# Barrier_control.net
KiCad netlist of a schematic drawn in Altium Designer
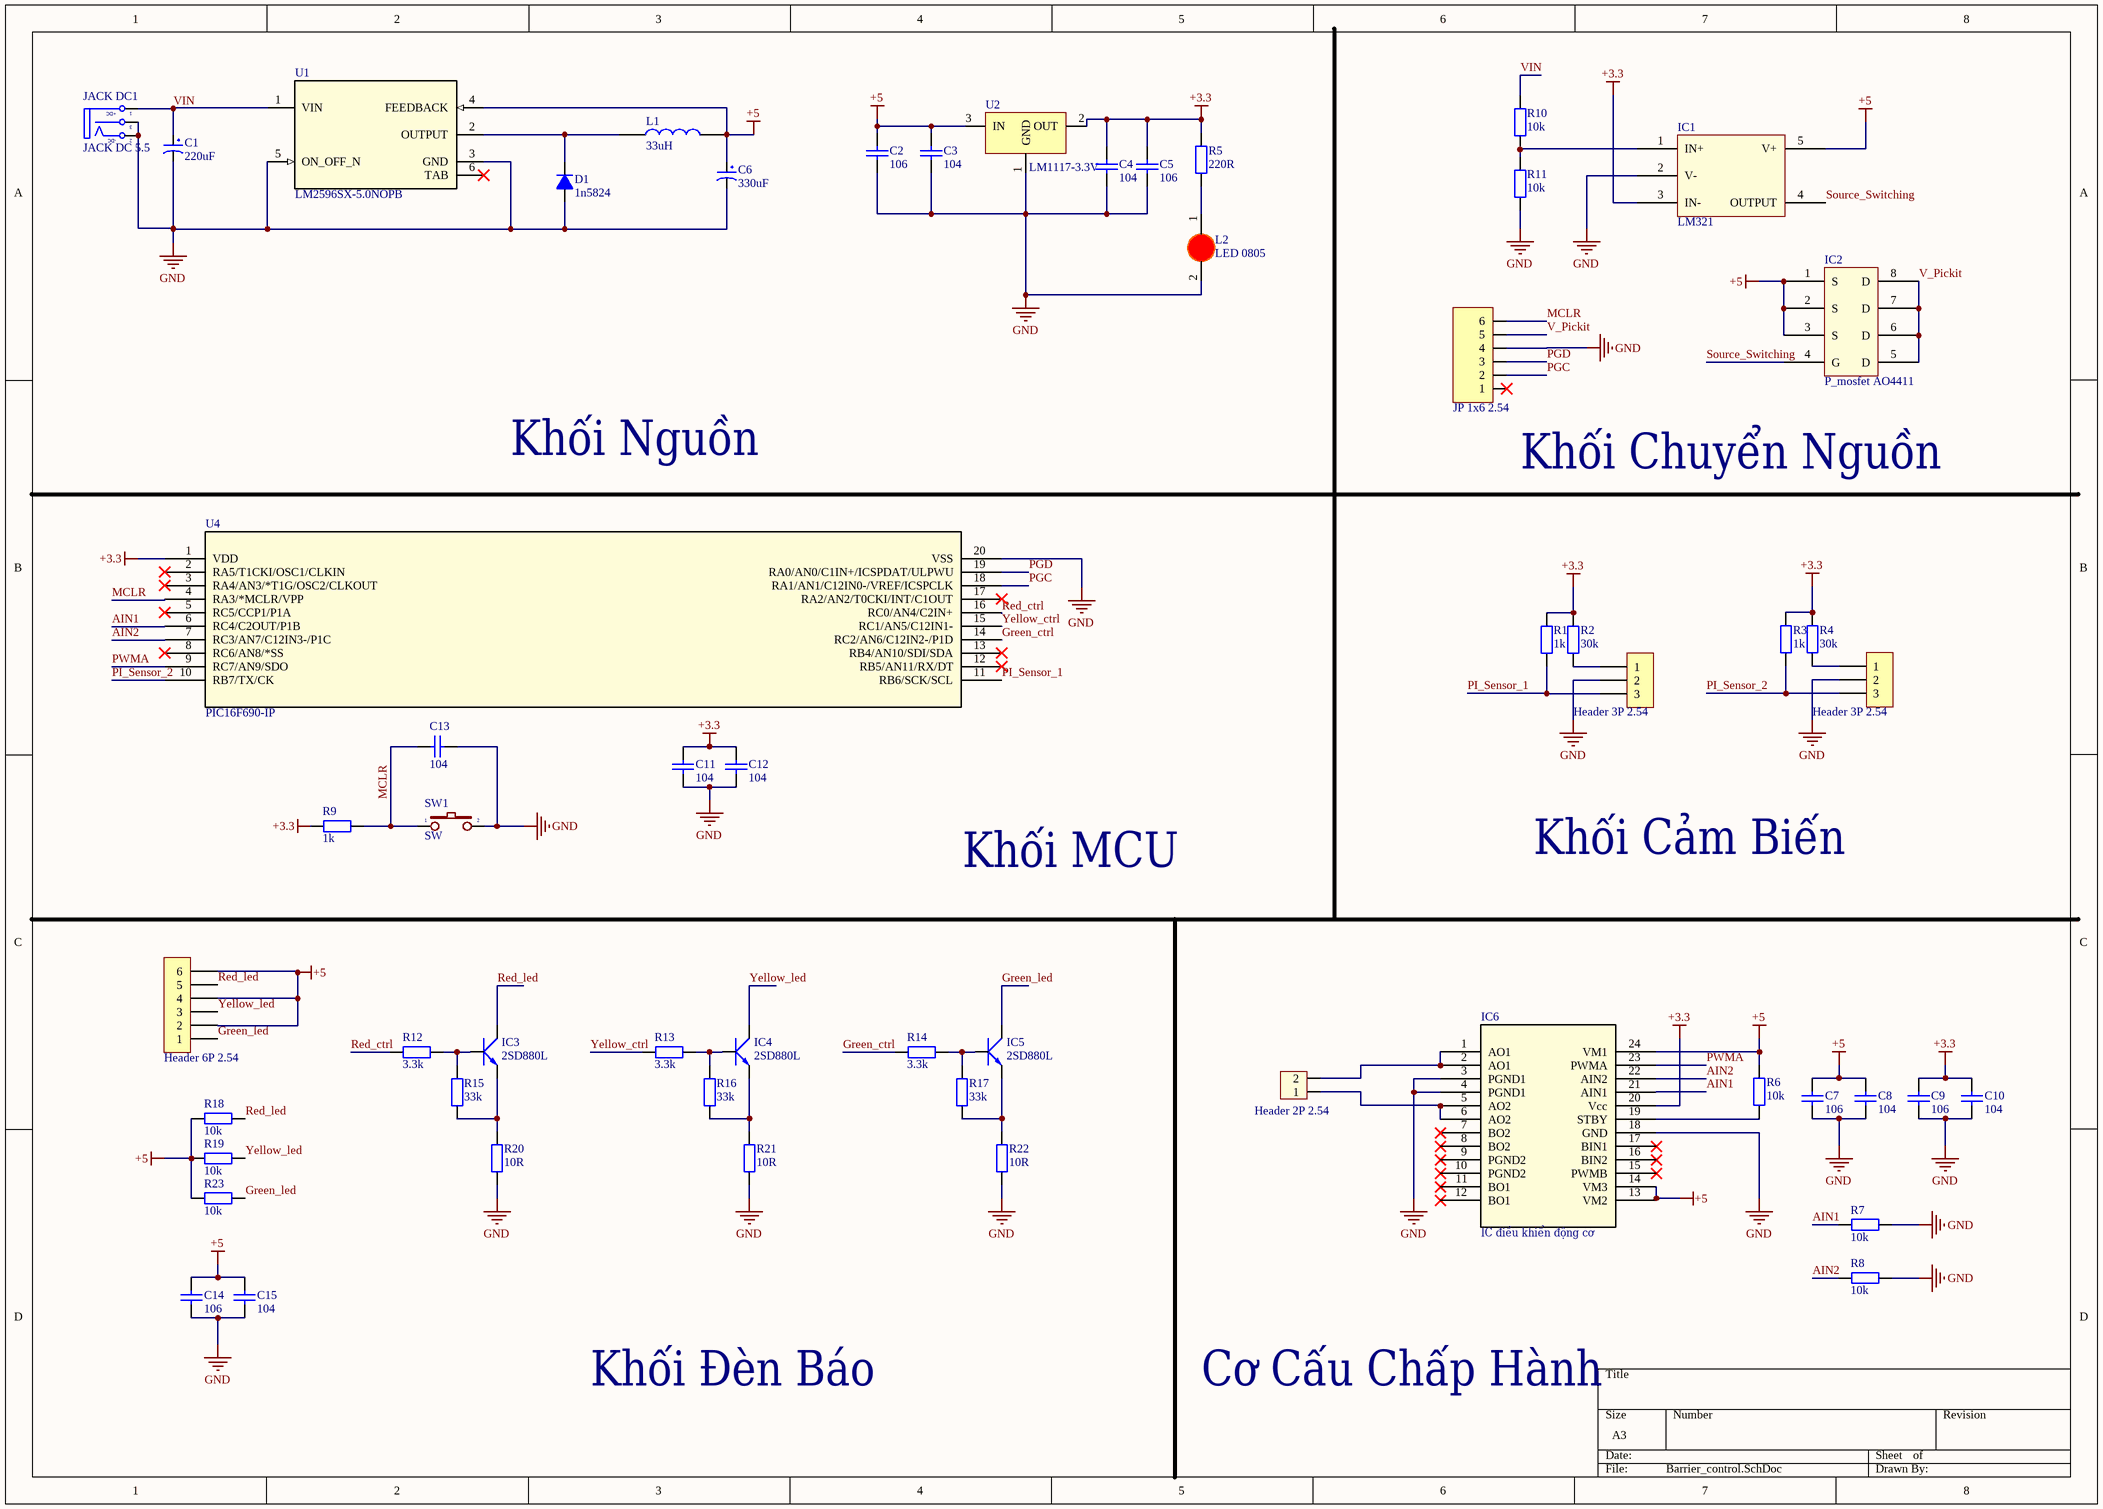
[diagram p0: Barrier_control.SchDoc]

(export (version "E")
  (design (tool "Eeschema 10.0.6"))
  (components
    (comp (ref "C1")
      (value "220uF")
      (footprint "tu hoa 6.5mm")
      (description "Cắm")
      (libsource (lib "Altium_Lib_by_KhueNguyenCreator") (part "Tu Hoa 220uF 16V 7x11"))
    )
    (comp (ref "C2")
      (value "106")
      (footprint "tu 1206")
      (description "Dán")
      (libsource (lib "Altium_Lib_by_KhueNguyenCreator") (part "Tu 1206 106 16V 20%"))
    )
    (comp (ref "C3")
      (value "104")
      (footprint "tu 1206")
      (description "Dán")
      (libsource (lib "Altium_Lib_by_KhueNguyenCreator") (part "Tu 1206 104 50V 20%"))
    )
    (comp (ref "C4")
      (value "104")
      (footprint "tu 1206")
      (description "Dán")
      (libsource (lib "Altium_Lib_by_KhueNguyenCreator") (part "Tu 1206 104 50V 20%"))
    )
    (comp (ref "C5")
      (value "106")
      (footprint "tu 1206")
      (description "Dán")
      (libsource (lib "Altium_Lib_by_KhueNguyenCreator") (part "Tu 1206 106 16V 20%"))
    )
    (comp (ref "C6")
      (value "330uF")
      (footprint "tu hoa 10mm")
      (description "Cắm")
      (libsource (lib "Altium_Lib_by_KhueNguyenCreator") (part "Tu Hoa 330uF 35V 10x12"))
    )
    (comp (ref "C7")
      (value "106")
      (footprint "tu 1206")
      (description "Dán")
      (libsource (lib "Altium_Lib_by_KhueNguyenCreator") (part "Tu 1206 106 16V 20%"))
    )
    (comp (ref "C8")
      (value "104")
      (footprint "tu 1206")
      (description "Dán")
      (libsource (lib "Altium_Lib_by_KhueNguyenCreator") (part "Tu 1206 104 50V 20%"))
    )
    (comp (ref "C9")
      (value "106")
      (footprint "tu 1206")
      (description "Dán")
      (libsource (lib "Altium_Lib_by_KhueNguyenCreator") (part "Tu 1206 106 16V 20%"))
    )
    (comp (ref "C10")
      (value "104")
      (footprint "tu 1206")
      (description "Dán")
      (libsource (lib "Altium_Lib_by_KhueNguyenCreator") (part "Tu 1206 104 50V 20%"))
    )
    (comp (ref "C11")
      (value "104")
      (footprint "tu 0805")
      (description "Dán")
      (libsource (lib "Altium_Lib_by_KhueNguyenCreator") (part "Tu 0805 104 50V 10%"))
    )
    (comp (ref "C12")
      (value "104")
      (footprint "tu 0805")
      (description "Dán")
      (libsource (lib "Altium_Lib_by_KhueNguyenCreator") (part "Tu 0805 104 50V 10%"))
    )
    (comp (ref "C13")
      (value "104")
      (footprint "tu gom")
      (description "Cắm")
      (libsource (lib "Altium_Lib_by_KhueNguyenCreator") (part "Tu gom 104 50V"))
    )
    (comp (ref "C14")
      (value "106")
      (footprint "tu 1206")
      (description "Dán")
      (libsource (lib "Altium_Lib_by_KhueNguyenCreator") (part "Tu 1206 106 16V 20%"))
    )
    (comp (ref "C15")
      (value "104")
      (footprint "tu 1206")
      (description "Dán")
      (libsource (lib "Altium_Lib_by_KhueNguyenCreator") (part "Tu 1206 104 50V 20%"))
    )
    (comp (ref "D1")
      (value "1n5824")
      (footprint "DIODE 1A")
      (description "Cắm")
      (libsource (lib "Altium_Lib_by_KhueNguyenCreator") (part "Diode 1N4007"))
    )
    (comp (ref "H1")
      (value "Header 3P 2.54")
      (footprint "XH2.54M-3")
      (description "Cắm")
      (libsource (lib "Altium_Lib_by_KhueNguyenCreator") (part "Header 3P 2.54 Duc Thang"))
    )
    (comp (ref "H2")
      (value "Header 3P 2.54")
      (footprint "XH2.54M-3")
      (description "Cắm")
      (libsource (lib "Altium_Lib_by_KhueNguyenCreator") (part "Header 3P 2.54 Duc Thang"))
    )
    (comp (ref "H3")
      (value "Header 2P 2.54")
      (footprint "XH2.54M-2")
      (description "Cắm")
      (libsource (lib "Altium_Lib_by_KhueNguyenCreator") (part "Header 2P 2.54 Duc Thang"))
    )
    (comp (ref "H4")
      (value "Header 6P 2.54")
      (footprint "XH2.54M-6")
      (description "Cắm")
      (libsource (lib "Altium_Lib_by_KhueNguyenCreator") (part "Header 6P 2.54 Duc Thang"))
    )
    (comp (ref "IC1") (value "LM321") (footprint "SOT23_LM321") (libsource (lib "Schlib2") (part "LM321")))
    (comp (ref "IC2")
      (value "P_mosfet AO4411")
      (footprint "SOIC8_AO4411")
      (libsource (lib "AO4411") (part "P_mosfet AO4411"))
    )
    (comp (ref "IC3")
      (value "2SD880L")
      (footprint "TO220")
      (libsource (lib "tran_npn_2SD880L") (part "transistor NPN"))
    )
    (comp (ref "IC4")
      (value "2SD880L")
      (footprint "TO220")
      (libsource (lib "tran_npn_2SD880L") (part "transistor NPN"))
    )
    (comp (ref "IC5")
      (value "2SD880L")
      (footprint "TO220")
      (libsource (lib "tran_npn_2SD880L") (part "transistor NPN"))
    )
    (comp (ref "IC6")
      (value "IC điều khiển động cơ")
      (footprint "SSOP24-P-300-0p65A_TOS")
      (libsource (lib "TB6612") (part "TB6612FNG"))
    )
    (comp (ref "JACK DC1")
      (value "JACK DC 5.5")
      (footprint "JACK DC 5.5")
      (libsource (lib "Altium_Lib_by_KhueNguyenCreator") (part "JACK DC 5.5"))
    )
    (comp (ref "JP1")
      (value "JP 1x6 2.54")
      (footprint "JP 1x6 DC")
      (description "Cắm")
      (libsource (lib "Altium_Lib_by_KhueNguyenCreator") (part "JP 1x6 2.54 Duc Cong"))
    )
    (comp (ref "L1")
      (value "33uH")
      (footprint "Cuon Cam 12x12x10")
      (description "Dán")
      (libsource (lib "Altium_Lib_by_KhueNguyenCreator") (part "CUON CAM 100uH SMD"))
    )
    (comp (ref "L2")
      (value "LED 0805")
      (footprint "LED-0805-Red")
      (description "Dán")
      (libsource (lib "Altium_Lib_by_KhueNguyenCreator") (part "LED 0805 Do"))
    )
    (comp (ref "R1")
      (value "1k")
      (footprint "tro smd 0805")
      (description "Dán")
      (libsource (lib "Altium_Lib_by_KhueNguyenCreator") (part "Tro 0805 1% 1k"))
    )
    (comp (ref "R2")
      (value "30k")
      (footprint "tro smd 0805")
      (description "Dán")
      (libsource (lib "Altium_Lib_by_KhueNguyenCreator") (part "Tro 0805 1% 33k"))
    )
    (comp (ref "R3")
      (value "1k")
      (footprint "tro smd 0805")
      (description "Dán")
      (libsource (lib "Altium_Lib_by_KhueNguyenCreator") (part "Tro 0805 1% 1k"))
    )
    (comp (ref "R4")
      (value "30k")
      (footprint "tro smd 0805")
      (description "Dán")
      (libsource (lib "Altium_Lib_by_KhueNguyenCreator") (part "Tro 0805 1% 33k"))
    )
    (comp (ref "R5")
      (value "220R")
      (footprint "tro smd 0805")
      (description "Dán")
      (libsource (lib "Altium_Lib_by_KhueNguyenCreator") (part "Tro 0805 1% 0.5R"))
    )
    (comp (ref "R6")
      (value "10k")
      (footprint "tro smd 0805")
      (description "Dán")
      (libsource (lib "Altium_Lib_by_KhueNguyenCreator") (part "Tro 0805 1% 10k"))
    )
    (comp (ref "R7")
      (value "10k")
      (footprint "tro smd 0805")
      (description "Dán")
      (libsource (lib "Altium_Lib_by_KhueNguyenCreator") (part "Tro 0805 1% 10k"))
    )
    (comp (ref "R8")
      (value "10k")
      (footprint "tro smd 0805")
      (description "Dán")
      (libsource (lib "Altium_Lib_by_KhueNguyenCreator") (part "Tro 0805 1% 10k"))
    )
    (comp (ref "R9")
      (value "1k")
      (footprint "tro smd 0805")
      (description "Dán")
      (libsource (lib "Altium_Lib_by_KhueNguyenCreator") (part "Tro 0805 1% 1k"))
    )
    (comp (ref "R10")
      (value "10k")
      (footprint "tro smd 0805")
      (description "Dán")
      (libsource (lib "Altium_Lib_by_KhueNguyenCreator") (part "Tro 0805 1% 10k"))
    )
    (comp (ref "R11")
      (value "10k")
      (footprint "tro smd 0805")
      (description "Dán")
      (libsource (lib "Altium_Lib_by_KhueNguyenCreator") (part "Tro 0805 1% 10k"))
    )
    (comp (ref "R12")
      (value "3.3k")
      (footprint "tro smd 0805")
      (description "Dán")
      (libsource (lib "Altium_Lib_by_KhueNguyenCreator") (part "Tro 0805 1% 3.3k"))
    )
    (comp (ref "R13")
      (value "3.3k")
      (footprint "tro smd 0805")
      (description "Dán")
      (libsource (lib "Altium_Lib_by_KhueNguyenCreator") (part "Tro 0805 1% 3.3k"))
    )
    (comp (ref "R14")
      (value "3.3k")
      (footprint "tro smd 0805")
      (description "Dán")
      (libsource (lib "Altium_Lib_by_KhueNguyenCreator") (part "Tro 0805 1% 3.3k"))
    )
    (comp (ref "R15")
      (value "33k")
      (footprint "tro smd 0805")
      (description "Dán")
      (libsource (lib "Altium_Lib_by_KhueNguyenCreator") (part "Tro 0805 1% 33k"))
    )
    (comp (ref "R16")
      (value "33k")
      (footprint "tro smd 0805")
      (description "Dán")
      (libsource (lib "Altium_Lib_by_KhueNguyenCreator") (part "Tro 0805 1% 33k"))
    )
    (comp (ref "R17")
      (value "33k")
      (footprint "tro smd 0805")
      (description "Dán")
      (libsource (lib "Altium_Lib_by_KhueNguyenCreator") (part "Tro 0805 1% 33k"))
    )
    (comp (ref "R18")
      (value "10k")
      (footprint "tro smd 0805")
      (description "Dán")
      (libsource (lib "Altium_Lib_by_KhueNguyenCreator") (part "Tro 0805 1% 10k"))
    )
    (comp (ref "R19")
      (value "10k")
      (footprint "tro smd 0805")
      (description "Dán")
      (libsource (lib "Altium_Lib_by_KhueNguyenCreator") (part "Tro 0805 1% 10k"))
    )
    (comp (ref "R20")
      (value "10R")
      (footprint "tro smd 0805")
      (description "Dán")
      (libsource (lib "Altium_Lib_by_KhueNguyenCreator") (part "Tro 0805 1% 10R"))
    )
    (comp (ref "R21")
      (value "10R")
      (footprint "tro smd 0805")
      (description "Dán")
      (libsource (lib "Altium_Lib_by_KhueNguyenCreator") (part "Tro 0805 1% 10R"))
    )
    (comp (ref "R22")
      (value "10R")
      (footprint "tro smd 0805")
      (description "Dán")
      (libsource (lib "Altium_Lib_by_KhueNguyenCreator") (part "Tro 0805 1% 10R"))
    )
    (comp (ref "R23")
      (value "10k")
      (footprint "tro smd 0805")
      (description "Dán")
      (libsource (lib "Altium_Lib_by_KhueNguyenCreator") (part "Tro 0805 1% 10k"))
    )
    (comp (ref "SW1")
      (value "SW")
      (footprint "SW2")
      (description "Switch button 2 pin")
      (libsource (lib "syhaunguyen") (part "SW2"))
    )
    (comp (ref "U1")
      (value "LM2596SX-5.0NOPB")
      (footprint "KTT0005B")
      (description "No Description Available")
      (fields
        (field (name "PARTNUMBER") "LM2596SX-ADJ/NOPB")
        (field (name "ALTERNATE_PARTNUMBER") "LM2596S-ADJ/NOPB")
      )
      (libsource (lib "LM2596SX-5P0NOPB") (part "LM2596SX-5.0NOPB"))
    )
    (comp (ref "U2")
      (value "LM1117-3.3V")
      (footprint "LM1117-SOP")
      (description "800mA Low-Dropout Linear Regulator")
      (fields (field (name "CREATOR") "Nguyen Ba Bien"))
      (libsource (lib "My library altium") (part "LM1117"))
    )
    (comp (ref "U4")
      (value "PIC16F690-IP")
      (footprint "PDIP20_300MC_MCH")
      (description "No Description Available")
      (libsource (lib "PIC16F690-IP") (part "PIC16F690-IP"))
    )
  )
  (nets
    (net (code "1") (name "+3.3") (class "Default")
      (node (ref "C10") (pin "1") (pinfunction "1_1") (pintype "passive"))
      (node (ref "C11") (pin "1") (pinfunction "1_1") (pintype "passive"))
      (node (ref "C12") (pin "1") (pinfunction "1_1") (pintype "passive"))
      (node (ref "C4") (pin "1") (pinfunction "1_1") (pintype "passive"))
      (node (ref "C5") (pin "2") (pinfunction "2_2") (pintype "passive"))
      (node (ref "C9") (pin "2") (pinfunction "2_2") (pintype "passive"))
      (node (ref "IC1") (pin "3") (pinfunction "IN-_3") (pintype "passive"))
      (node (ref "IC6") (pin "20") (pinfunction "Vcc_20") (pintype "passive"))
      (node (ref "R1") (pin "2") (pinfunction "2_2") (pintype "passive"))
      (node (ref "R2") (pin "2") (pinfunction "2_2") (pintype "passive"))
      (node (ref "R3") (pin "2") (pinfunction "2_2") (pintype "passive"))
      (node (ref "R4") (pin "2") (pinfunction "2_2") (pintype "passive"))
      (node (ref "R5") (pin "1") (pinfunction "1_1") (pintype "passive"))
      (node (ref "R9") (pin "2") (pinfunction "2_2") (pintype "passive"))
      (node (ref "U2") (pin "2") (pinfunction "OUT_2") (pintype "passive"))
      (node (ref "U4") (pin "1") (pinfunction "VDD_1") (pintype "passive"))
    )
    (net (code "2") (name "+5") (class "Default")
      (node (ref "C14") (pin "2") (pinfunction "2_2") (pintype "passive"))
      (node (ref "C15") (pin "1") (pinfunction "1_1") (pintype "passive"))
      (node (ref "C2") (pin "2") (pinfunction "2_2") (pintype "passive"))
      (node (ref "C3") (pin "1") (pinfunction "1_1") (pintype "passive"))
      (node (ref "C6") (pin "1") (pinfunction "1_1") (pintype "passive"))
      (node (ref "C7") (pin "2") (pinfunction "2_2") (pintype "passive"))
      (node (ref "C8") (pin "1") (pinfunction "1_1") (pintype "passive"))
      (node (ref "H4") (pin "2") (pinfunction "2_2") (pintype "passive"))
      (node (ref "H4") (pin "4") (pinfunction "4_4") (pintype "passive"))
      (node (ref "H4") (pin "6") (pinfunction "6_6") (pintype "passive"))
      (node (ref "IC1") (pin "5") (pinfunction "V+_5") (pintype "passive"))
      (node (ref "IC2") (pin "1") (pinfunction "S_1") (pintype "passive"))
      (node (ref "IC2") (pin "2") (pinfunction "S_2") (pintype "passive"))
      (node (ref "IC2") (pin "3") (pinfunction "S_3") (pintype "passive"))
      (node (ref "IC6") (pin "13") (pinfunction "VM2_13") (pintype "passive"))
      (node (ref "IC6") (pin "14") (pinfunction "VM3_14") (pintype "passive"))
      (node (ref "IC6") (pin "24") (pinfunction "VM1_24") (pintype "passive"))
      (node (ref "L1") (pin "2") (pinfunction "2_2") (pintype "passive"))
      (node (ref "R18") (pin "2") (pinfunction "2_2") (pintype "passive"))
      (node (ref "R19") (pin "2") (pinfunction "2_2") (pintype "passive"))
      (node (ref "R23") (pin "2") (pinfunction "2_2") (pintype "passive"))
      (node (ref "R6") (pin "2") (pinfunction "2_2") (pintype "passive"))
      (node (ref "U1") (pin "4") (pinfunction "FEEDBACK_4") (pintype "input"))
      (node (ref "U2") (pin "3") (pinfunction "IN_3") (pintype "passive"))
    )
    (net (code "3") (name "/AIN1") (class "Default")
      (node (ref "IC6") (pin "21") (pinfunction "AIN1_21") (pintype "passive"))
      (node (ref "R7") (pin "2") (pinfunction "2_2") (pintype "passive"))
      (node (ref "U4") (pin "6") (pinfunction "RC4/C2OUT/P1B_6") (pintype "passive"))
    )
    (net (code "4") (name "/AIN2") (class "Default")
      (node (ref "IC6") (pin "22") (pinfunction "AIN2_22") (pintype "passive"))
      (node (ref "R8") (pin "2") (pinfunction "2_2") (pintype "passive"))
      (node (ref "U4") (pin "7") (pinfunction "RC3/AN7/C12IN3-/P1C_7") (pintype "passive"))
    )
    (net (code "5") (name "/Green_ctrl") (class "Default")
      (node (ref "R14") (pin "1") (pinfunction "1_1") (pintype "passive"))
      (node (ref "U4") (pin "14") (pinfunction "RC2/AN6/C12IN2-/P1D_14") (pintype "passive"))
    )
    (net (code "6") (name "/Green_led") (class "Default")
      (node (ref "H4") (pin "1") (pinfunction "1_1") (pintype "passive"))
      (node (ref "IC5") (pin "3") (pinfunction "C_3") (pintype "passive"))
      (node (ref "R23") (pin "1") (pinfunction "1_1") (pintype "passive"))
    )
    (net (code "7") (name "/MCLR") (class "Default")
      (node (ref "C13") (pin "1") (pinfunction "1_1") (pintype "passive"))
      (node (ref "JP1") (pin "6") (pinfunction "6_6") (pintype "passive"))
      (node (ref "R9") (pin "1") (pinfunction "1_1") (pintype "passive"))
      (node (ref "SW1") (pin "1") (pinfunction "1_1") (pintype "passive"))
      (node (ref "U4") (pin "4") (pinfunction "RA3/*MCLR/VPP_4") (pintype "passive"))
    )
    (net (code "8") (name "/PGC") (class "Default")
      (node (ref "JP1") (pin "2") (pinfunction "2_2") (pintype "passive"))
      (node (ref "U4") (pin "18") (pinfunction "RA1/AN1/C12IN0-/VREF/ICSPCLK_18") (pintype "passive"))
    )
    (net (code "9") (name "/PGD") (class "Default")
      (node (ref "JP1") (pin "3") (pinfunction "3_3") (pintype "passive"))
      (node (ref "U4") (pin "19") (pinfunction "RA0/AN0/C1IN+/ICSPDAT/ULPWU_19") (pintype "passive"))
    )
    (net (code "10") (name "/PI_Sensor_1") (class "Default")
      (node (ref "H1") (pin "3") (pinfunction "3_3") (pintype "passive"))
      (node (ref "R1") (pin "1") (pinfunction "1_1") (pintype "passive"))
      (node (ref "U4") (pin "11") (pinfunction "RB6/SCK/SCL_11") (pintype "passive"))
    )
    (net (code "11") (name "/PI_Sensor_2") (class "Default")
      (node (ref "H2") (pin "3") (pinfunction "3_3") (pintype "passive"))
      (node (ref "R3") (pin "1") (pinfunction "1_1") (pintype "passive"))
      (node (ref "U4") (pin "10") (pinfunction "RB7/TX/CK_10") (pintype "passive"))
    )
    (net (code "12") (name "/PWMA") (class "Default")
      (node (ref "IC6") (pin "23") (pinfunction "PWMA_23") (pintype "passive"))
      (node (ref "U4") (pin "9") (pinfunction "RC7/AN9/SDO_9") (pintype "passive"))
    )
    (net (code "13") (name "/Red_ctrl") (class "Default")
      (node (ref "R12") (pin "1") (pinfunction "1_1") (pintype "passive"))
      (node (ref "U4") (pin "16") (pinfunction "RC0/AN4/C2IN+_16") (pintype "passive"))
    )
    (net (code "14") (name "/Red_led") (class "Default")
      (node (ref "H4") (pin "5") (pinfunction "5_5") (pintype "passive"))
      (node (ref "IC3") (pin "3") (pinfunction "C_3") (pintype "passive"))
      (node (ref "R18") (pin "1") (pinfunction "1_1") (pintype "passive"))
    )
    (net (code "15") (name "/Source_Switching") (class "Default")
      (node (ref "IC1") (pin "4") (pinfunction "OUTPUT_4") (pintype "passive"))
      (node (ref "IC2") (pin "4") (pinfunction "G_4") (pintype "passive"))
    )
    (net (code "16") (name "/VIN") (class "Default")
      (node (ref "C1") (pin "1") (pinfunction "1_1") (pintype "passive"))
      (node (ref "JACK DC1") (pin "1") (pinfunction "T_1") (pintype "passive"))
      (node (ref "R10") (pin "2") (pinfunction "2_2") (pintype "passive"))
      (node (ref "U1") (pin "1") (pinfunction "VIN_1") (pintype "power_in"))
    )
    (net (code "17") (name "/V_Pickit") (class "Default")
      (node (ref "IC2") (pin "5") (pinfunction "D_5") (pintype "passive"))
      (node (ref "IC2") (pin "6") (pinfunction "D_6") (pintype "passive"))
      (node (ref "IC2") (pin "7") (pinfunction "D_7") (pintype "passive"))
      (node (ref "IC2") (pin "8") (pinfunction "D_8") (pintype "passive"))
      (node (ref "JP1") (pin "5") (pinfunction "5_5") (pintype "passive"))
    )
    (net (code "18") (name "/Yellow_ctrl") (class "Default")
      (node (ref "R13") (pin "1") (pinfunction "1_1") (pintype "passive"))
      (node (ref "U4") (pin "15") (pinfunction "RC1/AN5/C12IN1-_15") (pintype "passive"))
    )
    (net (code "19") (name "/Yellow_led") (class "Default")
      (node (ref "H4") (pin "3") (pinfunction "3_3") (pintype "passive"))
      (node (ref "IC4") (pin "3") (pinfunction "C_3") (pintype "passive"))
      (node (ref "R19") (pin "1") (pinfunction "1_1") (pintype "passive"))
    )
    (net (code "20") (name "GND") (class "Default")
      (node (ref "C1") (pin "2") (pinfunction "2_2") (pintype "passive"))
      (node (ref "C10") (pin "2") (pinfunction "2_2") (pintype "passive"))
      (node (ref "C11") (pin "2") (pinfunction "2_2") (pintype "passive"))
      (node (ref "C12") (pin "2") (pinfunction "2_2") (pintype "passive"))
      (node (ref "C13") (pin "2") (pinfunction "2_2") (pintype "passive"))
      (node (ref "C14") (pin "1") (pinfunction "1_1") (pintype "passive"))
      (node (ref "C15") (pin "2") (pinfunction "2_2") (pintype "passive"))
      (node (ref "C2") (pin "1") (pinfunction "1_1") (pintype "passive"))
      (node (ref "C3") (pin "2") (pinfunction "2_2") (pintype "passive"))
      (node (ref "C4") (pin "2") (pinfunction "2_2") (pintype "passive"))
      (node (ref "C5") (pin "1") (pinfunction "1_1") (pintype "passive"))
      (node (ref "C6") (pin "2") (pinfunction "2_2") (pintype "passive"))
      (node (ref "C7") (pin "1") (pinfunction "1_1") (pintype "passive"))
      (node (ref "C8") (pin "2") (pinfunction "2_2") (pintype "passive"))
      (node (ref "C9") (pin "1") (pinfunction "1_1") (pintype "passive"))
      (node (ref "D1") (pin "1") (pinfunction "A_1") (pintype "passive"))
      (node (ref "H1") (pin "2") (pinfunction "2_2") (pintype "passive"))
      (node (ref "H2") (pin "2") (pinfunction "2_2") (pintype "passive"))
      (node (ref "IC1") (pin "2") (pinfunction "V-_2") (pintype "passive"))
      (node (ref "IC6") (pin "18") (pinfunction "GND_18") (pintype "passive"))
      (node (ref "IC6") (pin "3") (pinfunction "PGND1_3") (pintype "passive"))
      (node (ref "IC6") (pin "4") (pinfunction "PGND1_4") (pintype "passive"))
      (node (ref "JACK DC1") (pin "2") (pinfunction "TN_2") (pintype "passive"))
      (node (ref "JACK DC1") (pin "3") (pinfunction "S_3") (pintype "power_in"))
      (node (ref "JP1") (pin "4") (pinfunction "4_4") (pintype "passive"))
      (node (ref "L2") (pin "2") (pinfunction "K_2") (pintype "passive"))
      (node (ref "R11") (pin "1") (pinfunction "1_1") (pintype "passive"))
      (node (ref "R20") (pin "1") (pinfunction "1_1") (pintype "passive"))
      (node (ref "R21") (pin "1") (pinfunction "1_1") (pintype "passive"))
      (node (ref "R22") (pin "1") (pinfunction "1_1") (pintype "passive"))
      (node (ref "R7") (pin "1") (pinfunction "1_1") (pintype "passive"))
      (node (ref "R8") (pin "1") (pinfunction "1_1") (pintype "passive"))
      (node (ref "SW1") (pin "2") (pinfunction "2_2") (pintype "passive"))
      (node (ref "U1") (pin "3") (pinfunction "GND_3") (pintype "power_in"))
      (node (ref "U1") (pin "5") (pinfunction "ON_OFF_N_5") (pintype "input"))
      (node (ref "U2") (pin "1") (pinfunction "GND_1") (pintype "passive"))
      (node (ref "U4") (pin "20") (pinfunction "VSS_20") (pintype "passive"))
    )
    (net (code "21") (name "Net-(D1-K)") (class "Default")
      (node (ref "D1") (pin "2") (pinfunction "K_2") (pintype "passive"))
      (node (ref "L1") (pin "1") (pinfunction "1_1") (pintype "passive"))
      (node (ref "U1") (pin "2") (pinfunction "OUTPUT_2") (pintype "power_in"))
    )
    (net (code "22") (name "Net-(H1-Pad1)") (class "Default")
      (node (ref "H1") (pin "1") (pinfunction "1_1") (pintype "passive"))
      (node (ref "R2") (pin "1") (pinfunction "1_1") (pintype "passive"))
    )
    (net (code "23") (name "Net-(H2-Pad1)") (class "Default")
      (node (ref "H2") (pin "1") (pinfunction "1_1") (pintype "passive"))
      (node (ref "R4") (pin "1") (pinfunction "1_1") (pintype "passive"))
    )
    (net (code "24") (name "Net-(H3-Pad1)") (class "Default")
      (node (ref "H3") (pin "1") (pinfunction "1_1") (pintype "passive"))
      (node (ref "IC6") (pin "5") (pinfunction "AO2_5") (pintype "passive"))
      (node (ref "IC6") (pin "6") (pinfunction "AO2_6") (pintype "passive"))
    )
    (net (code "25") (name "Net-(H3-Pad2)") (class "Default")
      (node (ref "H3") (pin "2") (pinfunction "2_2") (pintype "passive"))
      (node (ref "IC6") (pin "1") (pinfunction "AO1_1") (pintype "passive"))
      (node (ref "IC6") (pin "2") (pinfunction "AO1_2") (pintype "passive"))
    )
    (net (code "26") (name "Net-(IC1-IN+)") (class "Default")
      (node (ref "IC1") (pin "1") (pinfunction "IN+_1") (pintype "passive"))
      (node (ref "R10") (pin "1") (pinfunction "1_1") (pintype "passive"))
      (node (ref "R11") (pin "2") (pinfunction "2_2") (pintype "passive"))
    )
    (net (code "27") (name "Net-(IC3-B)") (class "Default")
      (node (ref "IC3") (pin "1") (pinfunction "B_1") (pintype "passive"))
      (node (ref "R12") (pin "2") (pinfunction "2_2") (pintype "passive"))
      (node (ref "R15") (pin "2") (pinfunction "2_2") (pintype "passive"))
    )
    (net (code "28") (name "Net-(IC3-E)") (class "Default")
      (node (ref "IC3") (pin "2") (pinfunction "E_2") (pintype "passive"))
      (node (ref "R15") (pin "1") (pinfunction "1_1") (pintype "passive"))
      (node (ref "R20") (pin "2") (pinfunction "2_2") (pintype "passive"))
    )
    (net (code "29") (name "Net-(IC4-B)") (class "Default")
      (node (ref "IC4") (pin "1") (pinfunction "B_1") (pintype "passive"))
      (node (ref "R13") (pin "2") (pinfunction "2_2") (pintype "passive"))
      (node (ref "R16") (pin "2") (pinfunction "2_2") (pintype "passive"))
    )
    (net (code "30") (name "Net-(IC4-E)") (class "Default")
      (node (ref "IC4") (pin "2") (pinfunction "E_2") (pintype "passive"))
      (node (ref "R16") (pin "1") (pinfunction "1_1") (pintype "passive"))
      (node (ref "R21") (pin "2") (pinfunction "2_2") (pintype "passive"))
    )
    (net (code "31") (name "Net-(IC5-B)") (class "Default")
      (node (ref "IC5") (pin "1") (pinfunction "B_1") (pintype "passive"))
      (node (ref "R14") (pin "2") (pinfunction "2_2") (pintype "passive"))
      (node (ref "R17") (pin "2") (pinfunction "2_2") (pintype "passive"))
    )
    (net (code "32") (name "Net-(IC5-E)") (class "Default")
      (node (ref "IC5") (pin "2") (pinfunction "E_2") (pintype "passive"))
      (node (ref "R17") (pin "1") (pinfunction "1_1") (pintype "passive"))
      (node (ref "R22") (pin "2") (pinfunction "2_2") (pintype "passive"))
    )
    (net (code "33") (name "Net-(IC6-STBY)") (class "Default")
      (node (ref "IC6") (pin "19") (pinfunction "STBY_19") (pintype "passive"))
      (node (ref "R6") (pin "1") (pinfunction "1_1") (pintype "passive"))
    )
    (net (code "34") (name "Net-(L2-A)") (class "Default")
      (node (ref "L2") (pin "1") (pinfunction "A_1") (pintype "passive"))
      (node (ref "R5") (pin "2") (pinfunction "2_2") (pintype "passive"))
    )
    (net (code "35") (name "unconnected-(IC6-BIN1-Pad17)") (class "Default")
      (node (ref "IC6") (pin "17") (pinfunction "BIN1_17") (pintype "passive+no_connect"))
    )
    (net (code "36") (name "unconnected-(IC6-BIN2-Pad16)") (class "Default")
      (node (ref "IC6") (pin "16") (pinfunction "BIN2_16") (pintype "passive+no_connect"))
    )
    (net (code "37") (name "unconnected-(IC6-BO1-Pad11)") (class "Default")
      (node (ref "IC6") (pin "11") (pinfunction "BO1_11") (pintype "passive+no_connect"))
    )
    (net (code "38") (name "unconnected-(IC6-BO1-Pad12)") (class "Default")
      (node (ref "IC6") (pin "12") (pinfunction "BO1_12") (pintype "passive+no_connect"))
    )
    (net (code "39") (name "unconnected-(IC6-BO2-Pad7)") (class "Default")
      (node (ref "IC6") (pin "7") (pinfunction "BO2_7") (pintype "passive+no_connect"))
    )
    (net (code "40") (name "unconnected-(IC6-BO2-Pad8)") (class "Default")
      (node (ref "IC6") (pin "8") (pinfunction "BO2_8") (pintype "passive+no_connect"))
    )
    (net (code "41") (name "unconnected-(IC6-PGND2-Pad9)") (class "Default")
      (node (ref "IC6") (pin "9") (pinfunction "PGND2_9") (pintype "passive+no_connect"))
    )
    (net (code "42") (name "unconnected-(IC6-PGND2-Pad10)") (class "Default")
      (node (ref "IC6") (pin "10") (pinfunction "PGND2_10") (pintype "passive+no_connect"))
    )
    (net (code "43") (name "unconnected-(IC6-PWMB-Pad15)") (class "Default")
      (node (ref "IC6") (pin "15") (pinfunction "PWMB_15") (pintype "passive+no_connect"))
    )
    (net (code "44") (name "unconnected-(JP1-Pad1)") (class "Default")
      (node (ref "JP1") (pin "1") (pinfunction "1_1") (pintype "passive+no_connect"))
    )
    (net (code "45") (name "unconnected-(U1-TAB-Pad6)") (class "Default")
      (node (ref "U1") (pin "6") (pinfunction "TAB_6") (pintype "power_in+no_connect"))
    )
    (net (code "46") (name "unconnected-(U4-RA2{slash}AN2{slash}T0CKI{slash}INT{slash}C1OUT-Pad17)") (class "Default")
      (node (ref "U4") (pin "17") (pinfunction "RA2/AN2/T0CKI/INT/C1OUT_17") (pintype "passive+no_connect"))
    )
    (net (code "47") (name "unconnected-(U4-RA4{slash}AN3{slash}*T1G{slash}OSC2{slash}CLKOUT-Pad3)") (class "Default")
      (node (ref "U4") (pin "3") (pinfunction "RA4/AN3/*T1G/OSC2/CLKOUT_3") (pintype "passive+no_connect"))
    )
    (net (code "48") (name "unconnected-(U4-RA5{slash}T1CKI{slash}OSC1{slash}CLKIN-Pad2)") (class "Default")
      (node (ref "U4") (pin "2") (pinfunction "RA5/T1CKI/OSC1/CLKIN_2") (pintype "passive+no_connect"))
    )
    (net (code "49") (name "unconnected-(U4-RB4{slash}AN10{slash}SDI{slash}SDA-Pad13)") (class "Default")
      (node (ref "U4") (pin "13") (pinfunction "RB4/AN10/SDI/SDA_13") (pintype "passive+no_connect"))
    )
    (net (code "50") (name "unconnected-(U4-RB5{slash}AN11{slash}RX{slash}DT-Pad12)") (class "Default")
      (node (ref "U4") (pin "12") (pinfunction "RB5/AN11/RX/DT_12") (pintype "passive+no_connect"))
    )
    (net (code "51") (name "unconnected-(U4-RC5{slash}CCP1{slash}P1A-Pad5)") (class "Default")
      (node (ref "U4") (pin "5") (pinfunction "RC5/CCP1/P1A_5") (pintype "passive+no_connect"))
    )
    (net (code "52") (name "unconnected-(U4-RC6{slash}AN8{slash}*SS-Pad8)") (class "Default")
      (node (ref "U4") (pin "8") (pinfunction "RC6/AN8/*SS_8") (pintype "passive+no_connect"))
    )
  )
)
